# power_12V_5V_3V3_V10.net
KiCad netlist of a schematic drawn in Altium Designer
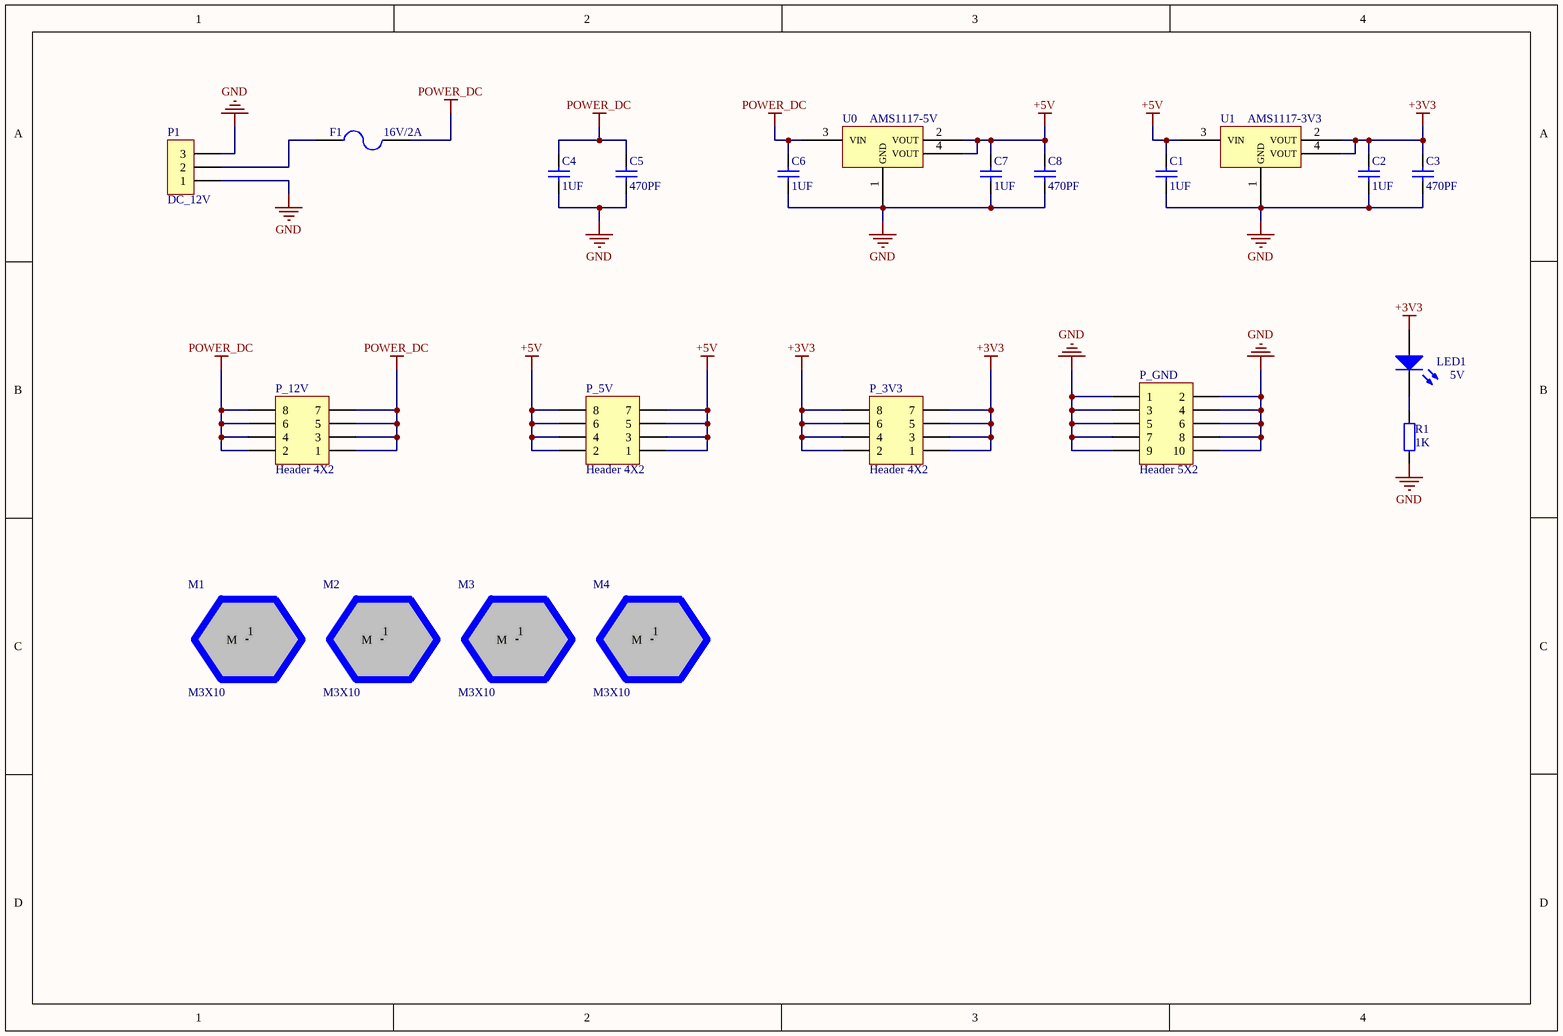
[diagram p0: power_12V_5V_3V3_V10.SchDoc]

(export (version "E")
  (design (tool "Eeschema 10.0.6"))
  (components
    (comp (ref "C1")
      (value "Cap")
      (footprint "C 0603_M")
      (description "Capacitor")
      (fields (field (name "ALTIUM_UNNAMED_1") "1UF") (field (name "PUBLISHER") "Altium Limited"))
      (libsource (lib "balanceDriver") (part "Cap"))
    )
    (comp (ref "C2")
      (value "Cap")
      (footprint "C 0603_M")
      (description "Capacitor")
      (fields (field (name "ALTIUM_UNNAMED_1") "1UF") (field (name "PUBLISHER") "Altium Limited"))
      (libsource (lib "balanceDriver") (part "Cap"))
    )
    (comp (ref "C3")
      (value "Cap")
      (footprint "C 0603_M")
      (description "Capacitor")
      (fields (field (name "ALTIUM_UNNAMED_1") "470PF") (field (name "PUBLISHER") "Altium Limited"))
      (libsource (lib "balanceDriver") (part "Cap"))
    )
    (comp (ref "C4")
      (value "Cap")
      (footprint "C 0603_M")
      (description "Capacitor")
      (fields (field (name "ALTIUM_UNNAMED_1") "1UF") (field (name "PUBLISHER") "Altium Limited"))
      (libsource (lib "balanceDriver") (part "Cap"))
    )
    (comp (ref "C5")
      (value "Cap")
      (footprint "C 0603_M")
      (description "Capacitor")
      (fields (field (name "ALTIUM_UNNAMED_1") "470PF") (field (name "PUBLISHER") "Altium Limited"))
      (libsource (lib "balanceDriver") (part "Cap"))
    )
    (comp (ref "C6")
      (value "Cap")
      (footprint "C 0603_M")
      (description "Capacitor")
      (fields (field (name "ALTIUM_UNNAMED_1") "1UF") (field (name "PUBLISHER") "Altium Limited"))
      (libsource (lib "balanceDriver") (part "Cap"))
    )
    (comp (ref "C7")
      (value "Cap")
      (footprint "C 0603_M")
      (description "Capacitor")
      (fields (field (name "ALTIUM_UNNAMED_1") "1UF") (field (name "PUBLISHER") "Altium Limited"))
      (libsource (lib "balanceDriver") (part "Cap"))
    )
    (comp (ref "C8")
      (value "Cap")
      (footprint "C 0603_M")
      (description "Capacitor")
      (fields (field (name "ALTIUM_UNNAMED_1") "470PF") (field (name "PUBLISHER") "Altium Limited"))
      (libsource (lib "balanceDriver") (part "Cap"))
    )
    (comp (ref "F1")
      (value "Fuse 2")
      (footprint "FU 1812")
      (description "Fuse")
      (fields (field (name "ALTIUM_UNNAMED_1") "16V/2A") (field (name "PUBLISHER") "Altium Limited"))
      (libsource (lib "Miscellaneous Devices") (part "Fuse 2"))
    )
    (comp (ref "LED1")
      (value "5V")
      (footprint "LED 0603Y")
      (description "Typical RED, GREEN, YELLOW, AMBER GaAs LED")
      (fields (field (name "PUBLISHER") "Altium Limited"))
      (libsource (lib "*") (part "LED2"))
    )
    (comp (ref "M1") (value "M3X10") (footprint "M3X10_L") (libsource (lib "stpper_ctrl") (part "M3X10")))
    (comp (ref "M2") (value "M3X10") (footprint "M3X10_L") (libsource (lib "stpper_ctrl") (part "M3X10")))
    (comp (ref "M3") (value "M3X10") (footprint "M3X10_L") (libsource (lib "stpper_ctrl") (part "M3X10")))
    (comp (ref "M4") (value "M3X10") (footprint "M3X10_L") (libsource (lib "stpper_ctrl") (part "M3X10")))
    (comp (ref "P1")
      (value "DC_12V")
      (footprint "DC-5MM")
      (libsource (lib "double_wheel_ctrl") (part "PIN3"))
    )
    (comp (ref "P_3V3")
      (value "Header 4X2")
      (footprint "HDR2.54-LI-2x4P")
      (description "Header, 4-Pin, Dual row")
      (fields (field (name "PUBLISHER") "Altium Limited"))
      (libsource (lib "Miscellaneous Connectors") (part "Header 4X2"))
    )
    (comp (ref "P_5V")
      (value "Header 4X2")
      (footprint "HDR2.54-LI-2x4P")
      (description "Header, 4-Pin, Dual row")
      (fields (field (name "PUBLISHER") "Altium Limited"))
      (libsource (lib "Miscellaneous Connectors") (part "Header 4X2"))
    )
    (comp (ref "P_12V")
      (value "Header 4X2")
      (footprint "HDR2.54-LI-2x4P")
      (description "Header, 4-Pin, Dual row")
      (fields (field (name "PUBLISHER") "Altium Limited"))
      (libsource (lib "Miscellaneous Connectors") (part "Header 4X2"))
    )
    (comp (ref "P_GND")
      (value "Header 5X2")
      (footprint "HDR2.54-LI-2x5P")
      (description "Header, 5-Pin, Dual row")
      (fields (field (name "PUBLISHER") "Altium Limited"))
      (libsource (lib "Miscellaneous Connectors") (part "Header 5X2"))
    )
    (comp (ref "R1")
      (value "1K")
      (footprint "R 0603-HP_M")
      (description "Resistor")
      (fields (field (name "PUBLISHER") "Altium Limited"))
      (libsource (lib "*") (part "Res2"))
    )
    (comp (ref "U0")
      (value "AMS1117-5V")
      (footprint "SOT223_M")
      (libsource (lib "power_12v_5V_3V3") (part "ASM1117-3V3"))
    )
    (comp (ref "U1")
      (value "AMS1117-3V3")
      (footprint "SOT223_M")
      (libsource (lib "power_12v_5V_3V3") (part "ASM1117-3V3"))
    )
  )
  (nets
    (net (code "1") (name "+3V3") (class "Default")
      (node (ref "C2") (pin "2") (pinfunction "2_2") (pintype "passive"))
      (node (ref "C3") (pin "2") (pinfunction "2_2") (pintype "passive"))
      (node (ref "LED1") (pin "1") (pinfunction "A_1") (pintype "passive"))
      (node (ref "P_3V3") (pin "1") (pinfunction "1_1") (pintype "passive"))
      (node (ref "P_3V3") (pin "2") (pinfunction "2_2") (pintype "passive"))
      (node (ref "P_3V3") (pin "3") (pinfunction "3_3") (pintype "passive"))
      (node (ref "P_3V3") (pin "4") (pinfunction "4_4") (pintype "passive"))
      (node (ref "P_3V3") (pin "5") (pinfunction "5_5") (pintype "passive"))
      (node (ref "P_3V3") (pin "6") (pinfunction "6_6") (pintype "passive"))
      (node (ref "P_3V3") (pin "7") (pinfunction "7_7") (pintype "passive"))
      (node (ref "P_3V3") (pin "8") (pinfunction "8_8") (pintype "passive"))
      (node (ref "U1") (pin "2") (pinfunction "VOUT_2") (pintype "passive"))
      (node (ref "U1") (pin "4") (pinfunction "VOUT_4") (pintype "passive"))
    )
    (net (code "2") (name "+5V") (class "Default")
      (node (ref "C1") (pin "2") (pinfunction "2_2") (pintype "passive"))
      (node (ref "C7") (pin "2") (pinfunction "2_2") (pintype "passive"))
      (node (ref "C8") (pin "2") (pinfunction "2_2") (pintype "passive"))
      (node (ref "P_5V") (pin "1") (pinfunction "1_1") (pintype "passive"))
      (node (ref "P_5V") (pin "2") (pinfunction "2_2") (pintype "passive"))
      (node (ref "P_5V") (pin "3") (pinfunction "3_3") (pintype "passive"))
      (node (ref "P_5V") (pin "4") (pinfunction "4_4") (pintype "passive"))
      (node (ref "P_5V") (pin "5") (pinfunction "5_5") (pintype "passive"))
      (node (ref "P_5V") (pin "6") (pinfunction "6_6") (pintype "passive"))
      (node (ref "P_5V") (pin "7") (pinfunction "7_7") (pintype "passive"))
      (node (ref "P_5V") (pin "8") (pinfunction "8_8") (pintype "passive"))
      (node (ref "U0") (pin "2") (pinfunction "VOUT_2") (pintype "passive"))
      (node (ref "U0") (pin "4") (pinfunction "VOUT_4") (pintype "passive"))
      (node (ref "U1") (pin "3") (pinfunction "VIN_3") (pintype "passive"))
    )
    (net (code "3") (name "GND") (class "Default")
      (node (ref "C1") (pin "1") (pinfunction "1_1") (pintype "passive"))
      (node (ref "C2") (pin "1") (pinfunction "1_1") (pintype "passive"))
      (node (ref "C3") (pin "1") (pinfunction "1_1") (pintype "passive"))
      (node (ref "C4") (pin "1") (pinfunction "1_1") (pintype "passive"))
      (node (ref "C5") (pin "1") (pinfunction "1_1") (pintype "passive"))
      (node (ref "C6") (pin "1") (pinfunction "1_1") (pintype "passive"))
      (node (ref "C7") (pin "1") (pinfunction "1_1") (pintype "passive"))
      (node (ref "C8") (pin "1") (pinfunction "1_1") (pintype "passive"))
      (node (ref "P1") (pin "1") (pinfunction "1_1") (pintype "passive"))
      (node (ref "P1") (pin "3") (pinfunction "3_3") (pintype "passive"))
      (node (ref "P_GND") (pin "1") (pinfunction "1_1") (pintype "passive"))
      (node (ref "P_GND") (pin "10") (pinfunction "10_10") (pintype "passive"))
      (node (ref "P_GND") (pin "2") (pinfunction "2_2") (pintype "passive"))
      (node (ref "P_GND") (pin "3") (pinfunction "3_3") (pintype "passive"))
      (node (ref "P_GND") (pin "4") (pinfunction "4_4") (pintype "passive"))
      (node (ref "P_GND") (pin "5") (pinfunction "5_5") (pintype "passive"))
      (node (ref "P_GND") (pin "6") (pinfunction "6_6") (pintype "passive"))
      (node (ref "P_GND") (pin "7") (pinfunction "7_7") (pintype "passive"))
      (node (ref "P_GND") (pin "8") (pinfunction "8_8") (pintype "passive"))
      (node (ref "P_GND") (pin "9") (pinfunction "9_9") (pintype "passive"))
      (node (ref "R1") (pin "1") (pinfunction "1_1") (pintype "passive"))
      (node (ref "U0") (pin "1") (pinfunction "GND_1") (pintype "passive"))
      (node (ref "U1") (pin "1") (pinfunction "GND_1") (pintype "passive"))
    )
    (net (code "4") (name "Net-(F1-Pad1)") (class "Default")
      (node (ref "F1") (pin "1") (pinfunction "1_1") (pintype "passive"))
      (node (ref "P1") (pin "2") (pinfunction "2_2") (pintype "passive"))
    )
    (net (code "5") (name "Net-(LED1-K)") (class "Default")
      (node (ref "LED1") (pin "2") (pinfunction "K_2") (pintype "passive"))
      (node (ref "R1") (pin "2") (pinfunction "2_2") (pintype "passive"))
    )
    (net (code "6") (name "POWER_DC") (class "Default")
      (node (ref "C4") (pin "2") (pinfunction "2_2") (pintype "passive"))
      (node (ref "C5") (pin "2") (pinfunction "2_2") (pintype "passive"))
      (node (ref "C6") (pin "2") (pinfunction "2_2") (pintype "passive"))
      (node (ref "F1") (pin "2") (pinfunction "2_2") (pintype "passive"))
      (node (ref "P_12V") (pin "1") (pinfunction "1_1") (pintype "passive"))
      (node (ref "P_12V") (pin "2") (pinfunction "2_2") (pintype "passive"))
      (node (ref "P_12V") (pin "3") (pinfunction "3_3") (pintype "passive"))
      (node (ref "P_12V") (pin "4") (pinfunction "4_4") (pintype "passive"))
      (node (ref "P_12V") (pin "5") (pinfunction "5_5") (pintype "passive"))
      (node (ref "P_12V") (pin "6") (pinfunction "6_6") (pintype "passive"))
      (node (ref "P_12V") (pin "7") (pinfunction "7_7") (pintype "passive"))
      (node (ref "P_12V") (pin "8") (pinfunction "8_8") (pintype "passive"))
      (node (ref "U0") (pin "3") (pinfunction "VIN_3") (pintype "passive"))
    )
    (net (code "7") (name "unconnected-(M1-M-Pad1)") (class "Default")
      (node (ref "M1") (pin "1") (pinfunction "M_1") (pintype "passive"))
    )
    (net (code "8") (name "unconnected-(M2-M-Pad1)") (class "Default")
      (node (ref "M2") (pin "1") (pinfunction "M_1") (pintype "passive"))
    )
    (net (code "9") (name "unconnected-(M3-M-Pad1)") (class "Default")
      (node (ref "M3") (pin "1") (pinfunction "M_1") (pintype "passive"))
    )
    (net (code "10") (name "unconnected-(M4-M-Pad1)") (class "Default")
      (node (ref "M4") (pin "1") (pinfunction "M_1") (pintype "passive"))
    )
  )
)
